# BPDC_mid.net
KiCad netlist of a schematic drawn in Altium Designer
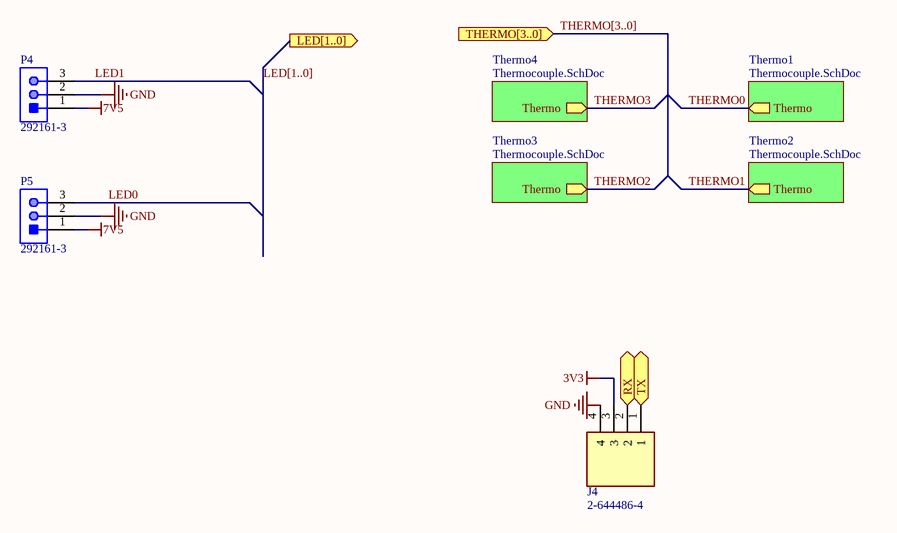
[diagram p0: BPDC mid.SchDoc]

(export (version "E")
  (design (tool "Eeschema 10.0.6"))
  (components
    (comp (ref "J4")
      (value "2-644486-4")
      (footprint "SamacSys:26444864")
      (description "Connector")
      (fields (field (name "MOUSER PART NUMBER") "571-2-644486-4"))
      (libsource (lib "*") (part "2-644486-4"))
    )
    (comp (ref "P4")
      (value "292161-3")
      (footprint "TECO-292161-3_V")
      (fields (field (name "MANUFACTURER") "TE Connectivity"))
      (libsource (lib "Altium Content Vault") (part "CN-1P-M-R3"))
    )
    (comp (ref "P5")
      (value "292161-3")
      (footprint "TECO-292161-3_V")
      (fields (field (name "MANUFACTURER") "TE Connectivity"))
      (libsource (lib "Altium Content Vault") (part "CN-1P-M-R3"))
    )
  )
  (nets
    (net (code "1") (name "/LED0") (class "Default")
      (node (ref "P5") (pin "3") (pinfunction "3_3") (pintype "passive"))
    )
    (net (code "2") (name "/LED1") (class "Default")
      (node (ref "P4") (pin "3") (pinfunction "3_3") (pintype "passive"))
    )
    (net (code "4") (name "/RX") (class "Default")
      (node (ref "J4") (pin "2") (pinfunction "2_2") (pintype "passive"))
    )
    (net (code "10") (name "/TX") (class "Default")
      (node (ref "J4") (pin "1") (pinfunction "1_1") (pintype "passive"))
    )
    (net (code "11") (name "3V3") (class "Default")
      (node (ref "J4") (pin "3") (pinfunction "3_3") (pintype "passive"))
    )
    (net (code "12") (name "7V5") (class "Default")
      (node (ref "P4") (pin "1") (pinfunction "1_1") (pintype "passive"))
      (node (ref "P5") (pin "1") (pinfunction "1_1") (pintype "passive"))
    )
    (net (code "13") (name "GND") (class "Default")
      (node (ref "J4") (pin "4") (pinfunction "4_4") (pintype "passive"))
      (node (ref "P4") (pin "2") (pinfunction "2_2") (pintype "passive"))
      (node (ref "P5") (pin "2") (pinfunction "2_2") (pintype "passive"))
    )
  )
)
